# onepiece.net
KiCad netlist of a schematic drawn in EAGLE
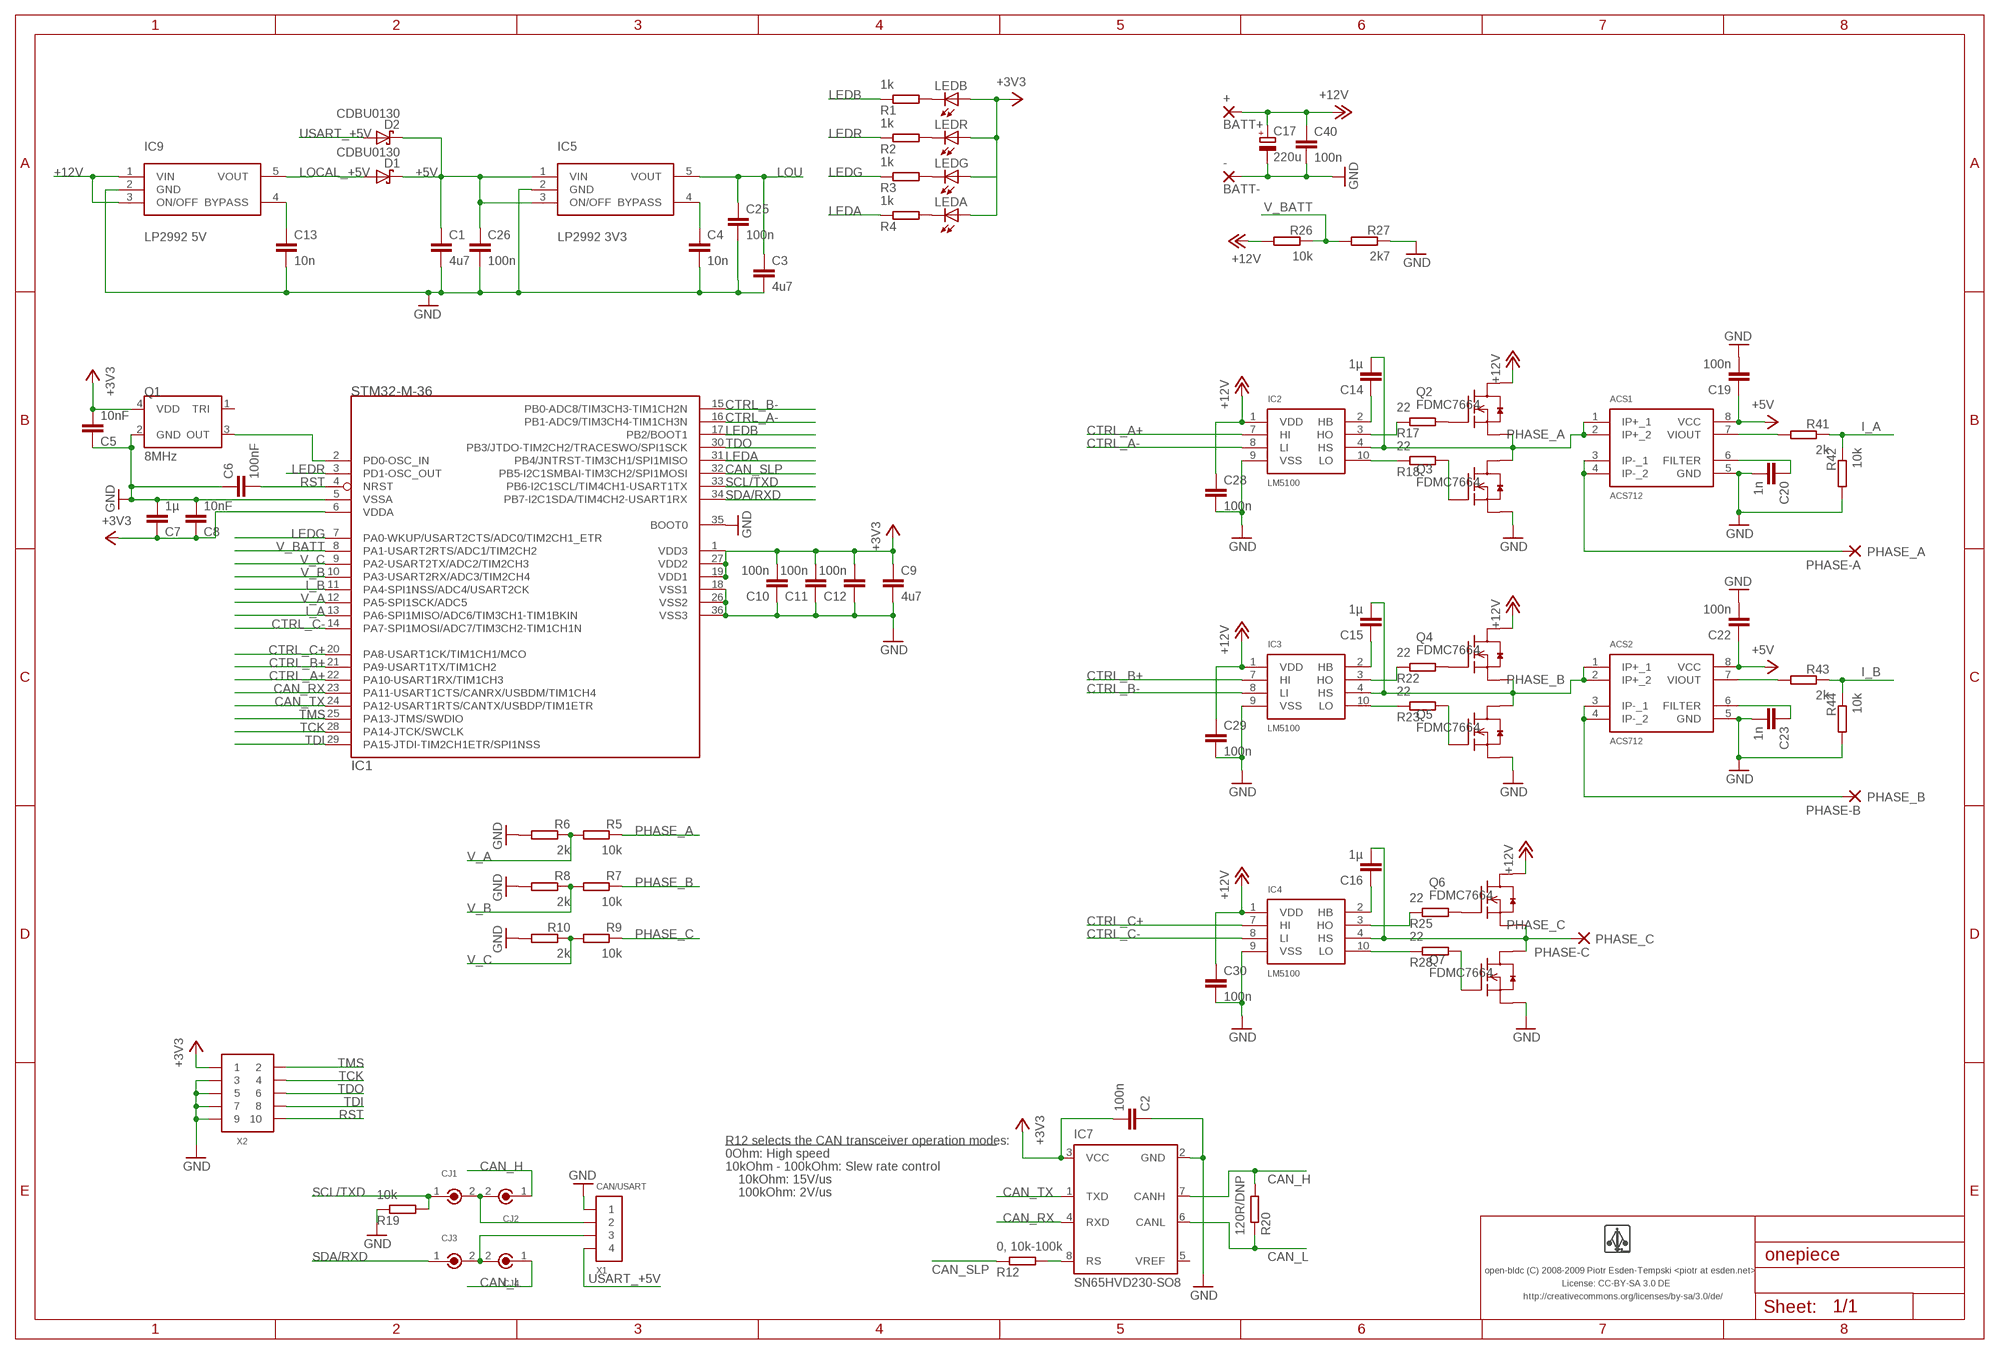
[diagram p0: schematic, sheet 1]

(export (version "E")
  (design (tool "Eeschema 10.0.6"))
  (components
    (comp (ref "+")
      (value "BATT+")
      (footprint "eagle-import:SMD2,54-5,08")
      (libsource (lib "eagle-import") (part "SMD5"))
    )
    (comp (ref "-")
      (value "BATT-")
      (footprint "eagle-import:SMD2,54-5,08")
      (libsource (lib "eagle-import") (part "SMD5"))
    )
    (comp (ref "ACS1")
      (value "ACS712")
      (footprint "eagle-import:SO8")
      (libsource (lib "eagle-import") (part "ACS712"))
    )
    (comp (ref "ACS2")
      (value "ACS712")
      (footprint "eagle-import:SO8")
      (libsource (lib "eagle-import") (part "ACS712"))
    )
    (comp (ref "C1")
      (value "4u7")
      (footprint "eagle-import:0603-CAP")
      (libsource (lib "eagle-import") (part "CAPACITOR-0603"))
    )
    (comp (ref "C2")
      (value "100n")
      (footprint "eagle-import:0603-CAP")
      (libsource (lib "eagle-import") (part "CAPACITOR-0603"))
    )
    (comp (ref "C3")
      (value "4u7")
      (footprint "eagle-import:0603-CAP")
      (libsource (lib "eagle-import") (part "CAPACITOR-0603"))
    )
    (comp (ref "C4")
      (value "10n")
      (footprint "eagle-import:0603-CAP")
      (libsource (lib "eagle-import") (part "CAPACITOR-0603"))
    )
    (comp (ref "C5")
      (value "10nF")
      (footprint "eagle-import:0603-CAP")
      (libsource (lib "eagle-import") (part "CAPACITOR-0603"))
    )
    (comp (ref "C6")
      (value "100nF")
      (footprint "eagle-import:0603-CAP")
      (libsource (lib "eagle-import") (part "CAPACITOR-0603"))
    )
    (comp (ref "C7")
      (value "1µ")
      (footprint "eagle-import:0603-CAP")
      (libsource (lib "eagle-import") (part "CAPACITOR-0603"))
    )
    (comp (ref "C8")
      (value "10nF")
      (footprint "eagle-import:0603-CAP")
      (libsource (lib "eagle-import") (part "CAPACITOR-0603"))
    )
    (comp (ref "C9")
      (value "4u7")
      (footprint "eagle-import:0603-CAP")
      (libsource (lib "eagle-import") (part "CAPACITOR-0603"))
    )
    (comp (ref "C10")
      (value "100n")
      (footprint "eagle-import:0603-CAP")
      (libsource (lib "eagle-import") (part "CAPACITOR-0603"))
    )
    (comp (ref "C11")
      (value "100n")
      (footprint "eagle-import:0603-CAP")
      (libsource (lib "eagle-import") (part "CAPACITOR-0603"))
    )
    (comp (ref "C12")
      (value "100n")
      (footprint "eagle-import:0603-CAP")
      (libsource (lib "eagle-import") (part "CAPACITOR-0603"))
    )
    (comp (ref "C13")
      (value "10n")
      (footprint "eagle-import:0603-CAP")
      (libsource (lib "eagle-import") (part "CAPACITOR-0603"))
    )
    (comp (ref "C14")
      (value "1µ")
      (footprint "eagle-import:0603-CAP")
      (libsource (lib "eagle-import") (part "CAPACITOR-0603"))
    )
    (comp (ref "C15")
      (value "1µ")
      (footprint "eagle-import:0603-CAP")
      (libsource (lib "eagle-import") (part "CAPACITOR-0603"))
    )
    (comp (ref "C16")
      (value "1µ")
      (footprint "eagle-import:0603-CAP")
      (libsource (lib "eagle-import") (part "CAPACITOR-0603"))
    )
    (comp (ref "C17")
      (value "220u")
      (footprint "eagle-import:7343_D")
      (libsource (lib "eagle-import") (part "CAPACITOR-POLD"))
    )
    (comp (ref "C19")
      (value "100n")
      (footprint "eagle-import:0603-CAP")
      (libsource (lib "eagle-import") (part "CAPACITOR-0603"))
    )
    (comp (ref "C20")
      (value "1n")
      (footprint "eagle-import:0603-CAP")
      (libsource (lib "eagle-import") (part "CAPACITOR-0603"))
    )
    (comp (ref "C22")
      (value "100n")
      (footprint "eagle-import:0603-CAP")
      (libsource (lib "eagle-import") (part "CAPACITOR-0603"))
    )
    (comp (ref "C23")
      (value "1n")
      (footprint "eagle-import:0603-CAP")
      (libsource (lib "eagle-import") (part "CAPACITOR-0603"))
    )
    (comp (ref "C25")
      (value "100n")
      (footprint "eagle-import:0603-CAP")
      (libsource (lib "eagle-import") (part "CAPACITOR-0603"))
    )
    (comp (ref "C26")
      (value "100n")
      (footprint "eagle-import:0603-CAP")
      (libsource (lib "eagle-import") (part "CAPACITOR-0603"))
    )
    (comp (ref "C28")
      (value "100n")
      (footprint "eagle-import:0603-CAP")
      (libsource (lib "eagle-import") (part "CAPACITOR-0603"))
    )
    (comp (ref "C29")
      (value "100n")
      (footprint "eagle-import:0603-CAP")
      (libsource (lib "eagle-import") (part "CAPACITOR-0603"))
    )
    (comp (ref "C30")
      (value "100n")
      (footprint "eagle-import:0603-CAP")
      (libsource (lib "eagle-import") (part "CAPACITOR-0603"))
    )
    (comp (ref "C40")
      (value "100n")
      (footprint "eagle-import:0603-CAP")
      (libsource (lib "eagle-import") (part "CAPACITOR-0603"))
    )
    (comp (ref "CJ1")
      (value "CIRC_JMP")
      (footprint "eagle-import:CIRC_JMP")
      (libsource (lib "eagle-import") (part "CIRC_JMP"))
    )
    (comp (ref "CJ2")
      (value "CIRC_JMP")
      (footprint "eagle-import:CIRC_JMP")
      (libsource (lib "eagle-import") (part "CIRC_JMP"))
    )
    (comp (ref "CJ3")
      (value "CIRC_JMP")
      (footprint "eagle-import:CIRC_JMP")
      (libsource (lib "eagle-import") (part "CIRC_JMP"))
    )
    (comp (ref "CJ4")
      (value "CIRC_JMP")
      (footprint "eagle-import:CIRC_JMP")
      (libsource (lib "eagle-import") (part "CIRC_JMP"))
    )
    (comp (ref "D1")
      (value "CDBU0130")
      (footprint "eagle-import:0603-LED")
      (libsource (lib "eagle-import") (part "CDBU0130"))
    )
    (comp (ref "D2")
      (value "CDBU0130")
      (footprint "eagle-import:0603-LED")
      (libsource (lib "eagle-import") (part "CDBU0130"))
    )
    (comp (ref "IC1")
      (value "STM32-M-36")
      (footprint "eagle-import:VFQFPN36-LP")
      (libsource (lib "eagle-import") (part "STM32-M-36"))
    )
    (comp (ref "IC2")
      (value "LM5100")
      (footprint "eagle-import:LLP-10")
      (libsource (lib "eagle-import") (part "LM5100"))
    )
    (comp (ref "IC3")
      (value "LM5100")
      (footprint "eagle-import:LLP-10")
      (libsource (lib "eagle-import") (part "LM5100"))
    )
    (comp (ref "IC4")
      (value "LM5100")
      (footprint "eagle-import:LLP-10")
      (libsource (lib "eagle-import") (part "LM5100"))
    )
    (comp (ref "IC5")
      (value "LP2992 3V3")
      (footprint "eagle-import:SOT23-5")
      (libsource (lib "eagle-import") (part "LP2992"))
    )
    (comp (ref "IC7")
      (value "SN65HVD230-SO8")
      (footprint "eagle-import:SO8")
      (libsource (lib "eagle-import") (part "SN65HVD230"))
    )
    (comp (ref "IC9")
      (value "LP2992 5V")
      (footprint "eagle-import:SOT23-5")
      (libsource (lib "eagle-import") (part "LP2992"))
    )
    (comp (ref "LEDA")
      (value "AMBER")
      (footprint "eagle-import:0603-LED")
      (libsource (lib "eagle-import") (part "LED"))
    )
    (comp (ref "LEDB")
      (value "BLUE")
      (footprint "eagle-import:0603-LED")
      (libsource (lib "eagle-import") (part "LED"))
    )
    (comp (ref "LEDG")
      (value "GREEN")
      (footprint "eagle-import:0603-LED")
      (libsource (lib "eagle-import") (part "LED"))
    )
    (comp (ref "LEDR")
      (value "RED")
      (footprint "eagle-import:0603-LED")
      (libsource (lib "eagle-import") (part "LED"))
    )
    (comp (ref "PHASE-A")
      (value "PHASE_A")
      (footprint "eagle-import:SMD2,54-5,08")
      (libsource (lib "eagle-import") (part "SMD5"))
    )
    (comp (ref "PHASE-B")
      (value "PHASE_B")
      (footprint "eagle-import:SMD2,54-5,08")
      (libsource (lib "eagle-import") (part "SMD5"))
    )
    (comp (ref "PHASE-C")
      (value "PHASE_C")
      (footprint "eagle-import:SMD2,54-5,08")
      (libsource (lib "eagle-import") (part "SMD5"))
    )
    (comp (ref "Q1")
      (value "8MHz")
      (footprint "eagle-import:ASE_OSCILLATOR")
      (libsource (lib "eagle-import") (part "ASE_ASCILLATOR"))
    )
    (comp (ref "Q2")
      (value "FDMC7664")
      (footprint "eagle-import:MLP33")
      (libsource (lib "eagle-import") (part "FDMC7664"))
    )
    (comp (ref "Q3")
      (value "FDMC7664")
      (footprint "eagle-import:MLP33")
      (libsource (lib "eagle-import") (part "FDMC7664"))
    )
    (comp (ref "Q4")
      (value "FDMC7664")
      (footprint "eagle-import:MLP33")
      (libsource (lib "eagle-import") (part "FDMC7664"))
    )
    (comp (ref "Q5")
      (value "FDMC7664")
      (footprint "eagle-import:MLP33")
      (libsource (lib "eagle-import") (part "FDMC7664"))
    )
    (comp (ref "Q6")
      (value "FDMC7664")
      (footprint "eagle-import:MLP33")
      (libsource (lib "eagle-import") (part "FDMC7664"))
    )
    (comp (ref "Q7")
      (value "FDMC7664")
      (footprint "eagle-import:MLP33")
      (libsource (lib "eagle-import") (part "FDMC7664"))
    )
    (comp (ref "R1")
      (value "1k")
      (footprint "eagle-import:0603-RES")
      (libsource (lib "eagle-import") (part "RESISTOR-0603"))
    )
    (comp (ref "R2")
      (value "1k")
      (footprint "eagle-import:0603-RES")
      (libsource (lib "eagle-import") (part "RESISTOR-0603"))
    )
    (comp (ref "R3")
      (value "1k")
      (footprint "eagle-import:0603-RES")
      (libsource (lib "eagle-import") (part "RESISTOR-0603"))
    )
    (comp (ref "R4")
      (value "1k")
      (footprint "eagle-import:0603-RES")
      (libsource (lib "eagle-import") (part "RESISTOR-0603"))
    )
    (comp (ref "R5")
      (value "10k")
      (footprint "eagle-import:0603-RES")
      (libsource (lib "eagle-import") (part "RESISTOR-0603"))
    )
    (comp (ref "R6")
      (value "2k")
      (footprint "eagle-import:0603-RES")
      (libsource (lib "eagle-import") (part "RESISTOR-0603"))
    )
    (comp (ref "R7")
      (value "10k")
      (footprint "eagle-import:0603-RES")
      (libsource (lib "eagle-import") (part "RESISTOR-0603"))
    )
    (comp (ref "R8")
      (value "2k")
      (footprint "eagle-import:0603-RES")
      (libsource (lib "eagle-import") (part "RESISTOR-0603"))
    )
    (comp (ref "R9")
      (value "10k")
      (footprint "eagle-import:0603-RES")
      (libsource (lib "eagle-import") (part "RESISTOR-0603"))
    )
    (comp (ref "R10")
      (value "2k")
      (footprint "eagle-import:0603-RES")
      (libsource (lib "eagle-import") (part "RESISTOR-0603"))
    )
    (comp (ref "R12")
      (value "0, 10k-100k")
      (footprint "eagle-import:0603-RES")
      (libsource (lib "eagle-import") (part "RESISTOR-0603"))
    )
    (comp (ref "R17")
      (value "22")
      (footprint "eagle-import:0603-RES")
      (libsource (lib "eagle-import") (part "RESISTOR-0603"))
    )
    (comp (ref "R18")
      (value "22")
      (footprint "eagle-import:0603-RES")
      (libsource (lib "eagle-import") (part "RESISTOR-0603"))
    )
    (comp (ref "R19")
      (value "10k")
      (footprint "eagle-import:0603-RES")
      (libsource (lib "eagle-import") (part "RESISTOR-0603"))
    )
    (comp (ref "R20")
      (value "120R/DNP")
      (footprint "eagle-import:0603-RES")
      (libsource (lib "eagle-import") (part "RESISTOR-0603"))
    )
    (comp (ref "R22")
      (value "22")
      (footprint "eagle-import:0603-RES")
      (libsource (lib "eagle-import") (part "RESISTOR-0603"))
    )
    (comp (ref "R23")
      (value "22")
      (footprint "eagle-import:0603-RES")
      (libsource (lib "eagle-import") (part "RESISTOR-0603"))
    )
    (comp (ref "R25")
      (value "22")
      (footprint "eagle-import:0603-RES")
      (libsource (lib "eagle-import") (part "RESISTOR-0603"))
    )
    (comp (ref "R26")
      (value "10k")
      (footprint "eagle-import:0603-RES")
      (libsource (lib "eagle-import") (part "RESISTOR-0603"))
    )
    (comp (ref "R27")
      (value "2k7")
      (footprint "eagle-import:0603-RES")
      (libsource (lib "eagle-import") (part "RESISTOR-0603"))
    )
    (comp (ref "R28")
      (value "22")
      (footprint "eagle-import:0603-RES")
      (libsource (lib "eagle-import") (part "RESISTOR-0603"))
    )
    (comp (ref "R41")
      (value "2k")
      (footprint "eagle-import:0603-RES")
      (libsource (lib "eagle-import") (part "RESISTOR-0603"))
    )
    (comp (ref "R42")
      (value "10k")
      (footprint "eagle-import:0603-RES")
      (libsource (lib "eagle-import") (part "RESISTOR-0603"))
    )
    (comp (ref "R43")
      (value "2k")
      (footprint "eagle-import:0603-RES")
      (libsource (lib "eagle-import") (part "RESISTOR-0603"))
    )
    (comp (ref "R44")
      (value "10k")
      (footprint "eagle-import:0603-RES")
      (libsource (lib "eagle-import") (part "RESISTOR-0603"))
    )
    (comp (ref "U$1")
      (value "LOGO")
      (footprint "eagle-import:LOGO_SMALL")
      (libsource (lib "eagle-import") (part "LOGO-SMALL"))
    )
    (comp (ref "X1")
      (value "CAN/USART")
      (footprint "eagle-import:PB-53261-04")
      (libsource (lib "eagle-import") (part "CONN_4-1-53261"))
    )
    (comp (ref "X2")
      (value "PIN_HDR_EDG_1.27MM_5-2")
      (footprint "eagle-import:PIN_HDR_1.27MM_SMD_DH_10")
      (libsource (lib "eagle-import") (part "PIN_HDR_EDG_1.27MM_5-2-DH"))
    )
  )
  (nets
    (net (code "1") (name "+3V3") (class "Default")
      (node (ref "C10") (pin "P$2") (pinfunction "2_P$2") (pintype "passive"))
      (node (ref "C11") (pin "P$2") (pinfunction "2_P$2") (pintype "passive"))
      (node (ref "C12") (pin "P$2") (pinfunction "2_P$2") (pintype "passive"))
      (node (ref "C2") (pin "P$2") (pinfunction "2_P$2") (pintype "passive"))
      (node (ref "C25") (pin "P$1") (pinfunction "1_P$1") (pintype "passive"))
      (node (ref "C3") (pin "P$1") (pinfunction "1_P$1") (pintype "passive"))
      (node (ref "C5") (pin "P$2") (pinfunction "2_P$2") (pintype "passive"))
      (node (ref "C7") (pin "P$1") (pinfunction "1_P$1") (pintype "passive"))
      (node (ref "C8") (pin "P$1") (pinfunction "1_P$1") (pintype "passive"))
      (node (ref "C9") (pin "P$1") (pinfunction "1_P$1") (pintype "passive"))
      (node (ref "IC1") (pin "1") (pinfunction "VDD3_1") (pintype "power_in"))
      (node (ref "IC1") (pin "19") (pinfunction "VDD1_19") (pintype "power_in"))
      (node (ref "IC1") (pin "27") (pinfunction "VDD2_27") (pintype "power_in"))
      (node (ref "IC1") (pin "6") (pinfunction "VDDA_6") (pintype "power_in"))
      (node (ref "IC5") (pin "5") (pinfunction "VOUT_5") (pintype "bidirectional"))
      (node (ref "IC7") (pin "3") (pinfunction "VCC_3") (pintype "power_in"))
      (node (ref "LEDA") (pin "A") (pinfunction "A_A") (pintype "passive"))
      (node (ref "LEDB") (pin "A") (pinfunction "A_A") (pintype "passive"))
      (node (ref "LEDG") (pin "A") (pinfunction "A_A") (pintype "passive"))
      (node (ref "LEDR") (pin "A") (pinfunction "A_A") (pintype "passive"))
      (node (ref "Q1") (pin "4") (pinfunction "VDD_4") (pintype "power_in"))
      (node (ref "X2") (pin "1") (pinfunction "1_1") (pintype "bidirectional"))
    )
    (net (code "2") (name "+5V") (class "Default")
      (node (ref "ACS1") (pin "8") (pinfunction "VCC_8") (pintype "bidirectional"))
      (node (ref "ACS2") (pin "8") (pinfunction "VCC_8") (pintype "bidirectional"))
      (node (ref "C1") (pin "P$1") (pinfunction "1_P$1") (pintype "passive"))
      (node (ref "C19") (pin "P$1") (pinfunction "1_P$1") (pintype "passive"))
      (node (ref "C22") (pin "P$1") (pinfunction "1_P$1") (pintype "passive"))
      (node (ref "C26") (pin "P$1") (pinfunction "1_P$1") (pintype "passive"))
      (node (ref "D1") (pin "C") (pinfunction "C_C") (pintype "passive"))
      (node (ref "D2") (pin "C") (pinfunction "C_C") (pintype "passive"))
      (node (ref "IC5") (pin "1") (pinfunction "VIN_1") (pintype "bidirectional"))
      (node (ref "IC5") (pin "3") (pinfunction "ON/OFF_3") (pintype "bidirectional"))
    )
    (net (code "3") (name "+12V") (class "Default")
      (node (ref "+") (pin "1") (pinfunction "P_1") (pintype "passive"))
      (node (ref "C17") (pin "+") (pinfunction "+_+") (pintype "passive"))
      (node (ref "C28") (pin "P$1") (pinfunction "1_P$1") (pintype "passive"))
      (node (ref "C29") (pin "P$1") (pinfunction "1_P$1") (pintype "passive"))
      (node (ref "C30") (pin "P$1") (pinfunction "1_P$1") (pintype "passive"))
      (node (ref "C40") (pin "P$1") (pinfunction "1_P$1") (pintype "passive"))
      (node (ref "IC2") (pin "1") (pinfunction "VDD_1") (pintype "bidirectional"))
      (node (ref "IC3") (pin "1") (pinfunction "VDD_1") (pintype "bidirectional"))
      (node (ref "IC4") (pin "1") (pinfunction "VDD_1") (pintype "bidirectional"))
      (node (ref "IC9") (pin "1") (pinfunction "VIN_1") (pintype "bidirectional"))
      (node (ref "IC9") (pin "3") (pinfunction "ON/OFF_3") (pintype "bidirectional"))
      (node (ref "Q2") (pin "5678D") (pinfunction "D_5678D") (pintype "passive"))
      (node (ref "Q4") (pin "5678D") (pinfunction "D_5678D") (pintype "passive"))
      (node (ref "Q6") (pin "5678D") (pinfunction "D_5678D") (pintype "passive"))
      (node (ref "R26") (pin "P$2") (pinfunction "2_P$2") (pintype "passive"))
    )
    (net (code "4") (name "/CAN_H") (class "Default")
      (node (ref "CJ2") (pin "1") (pinfunction "P$1_1") (pintype "bidirectional"))
      (node (ref "IC7") (pin "7") (pinfunction "CANH_7") (pintype "bidirectional"))
      (node (ref "R20") (pin "P$2") (pinfunction "2_P$2") (pintype "passive"))
    )
    (net (code "5") (name "/CAN_L") (class "Default")
      (node (ref "CJ4") (pin "1") (pinfunction "P$1_1") (pintype "bidirectional"))
      (node (ref "IC7") (pin "6") (pinfunction "CANL_6") (pintype "bidirectional"))
      (node (ref "R20") (pin "P$1") (pinfunction "1_P$1") (pintype "passive"))
    )
    (net (code "6") (name "/CAN_RX") (class "Default")
      (node (ref "IC1") (pin "23") (pinfunction "PA11-USART1CTS/CANRX/USBDM/TIM1CH4_23") (pintype "bidirectional"))
      (node (ref "IC7") (pin "4") (pinfunction "RXD_4") (pintype "output"))
    )
    (net (code "7") (name "/CAN_SLP") (class "Default")
      (node (ref "IC1") (pin "32") (pinfunction "PB5-I2C1SMBAI-TIM3CH2/SPI1MOSI_32") (pintype "bidirectional"))
      (node (ref "R12") (pin "P$1") (pinfunction "1_P$1") (pintype "passive"))
    )
    (net (code "8") (name "/CAN_TX") (class "Default")
      (node (ref "IC1") (pin "24") (pinfunction "PA12-USART1RTS/CANTX/USBDP/TIM1ETR_24") (pintype "bidirectional"))
      (node (ref "IC7") (pin "1") (pinfunction "TXD_1") (pintype "input"))
    )
    (net (code "9") (name "/CTRL_A+") (class "Default")
      (node (ref "IC1") (pin "22") (pinfunction "PA10-USART1RX/TIM1CH3_22") (pintype "bidirectional"))
      (node (ref "IC2") (pin "7") (pinfunction "HI_7") (pintype "bidirectional"))
    )
    (net (code "10") (name "/CTRL_A-") (class "Default")
      (node (ref "IC1") (pin "16") (pinfunction "PB1-ADC9/TIM3CH4-TIM1CH3N_16") (pintype "bidirectional"))
      (node (ref "IC2") (pin "8") (pinfunction "LI_8") (pintype "bidirectional"))
    )
    (net (code "11") (name "/CTRL_B+") (class "Default")
      (node (ref "IC1") (pin "21") (pinfunction "PA9-USART1TX/TIM1CH2_21") (pintype "bidirectional"))
      (node (ref "IC3") (pin "7") (pinfunction "HI_7") (pintype "bidirectional"))
    )
    (net (code "12") (name "/CTRL_B-") (class "Default")
      (node (ref "IC1") (pin "15") (pinfunction "PB0-ADC8/TIM3CH3-TIM1CH2N_15") (pintype "bidirectional"))
      (node (ref "IC3") (pin "8") (pinfunction "LI_8") (pintype "bidirectional"))
    )
    (net (code "13") (name "/CTRL_C+") (class "Default")
      (node (ref "IC1") (pin "20") (pinfunction "PA8-USART1CK/TIM1CH1/MCO_20") (pintype "bidirectional"))
      (node (ref "IC4") (pin "7") (pinfunction "HI_7") (pintype "bidirectional"))
    )
    (net (code "14") (name "/CTRL_C-") (class "Default")
      (node (ref "IC1") (pin "14") (pinfunction "PA7-SPI1MOSI/ADC7/TIM3CH2-TIM1CH1N_14") (pintype "bidirectional"))
      (node (ref "IC4") (pin "8") (pinfunction "LI_8") (pintype "bidirectional"))
    )
    (net (code "15") (name "/I_A") (class "Default")
      (node (ref "IC1") (pin "13") (pinfunction "PA6-SPI1MISO/ADC6/TIM3CH1-TIM1BKIN_13") (pintype "bidirectional"))
      (node (ref "R41") (pin "P$1") (pinfunction "1_P$1") (pintype "passive"))
      (node (ref "R42") (pin "P$1") (pinfunction "1_P$1") (pintype "passive"))
    )
    (net (code "16") (name "/I_B") (class "Default")
      (node (ref "IC1") (pin "11") (pinfunction "PA4-SPI1NSS/ADC4/USART2CK_11") (pintype "bidirectional"))
      (node (ref "R43") (pin "P$1") (pinfunction "1_P$1") (pintype "passive"))
      (node (ref "R44") (pin "P$1") (pinfunction "1_P$1") (pintype "passive"))
    )
    (net (code "17") (name "/LEDA") (class "Default")
      (node (ref "IC1") (pin "31") (pinfunction "PB4/JNTRST-TIM3CH1/SPI1MISO_31") (pintype "bidirectional"))
      (node (ref "R4") (pin "P$1") (pinfunction "1_P$1") (pintype "passive"))
    )
    (net (code "18") (name "/LEDB") (class "Default")
      (node (ref "IC1") (pin "17") (pinfunction "PB2/BOOT1_17") (pintype "bidirectional"))
      (node (ref "R1") (pin "P$1") (pinfunction "1_P$1") (pintype "passive"))
    )
    (net (code "19") (name "/LEDG") (class "Default")
      (node (ref "IC1") (pin "7") (pinfunction "PA0-WKUP/USART2CTS/ADC0/TIM2CH1_ETR_7") (pintype "bidirectional"))
      (node (ref "R3") (pin "P$1") (pinfunction "1_P$1") (pintype "passive"))
    )
    (net (code "20") (name "/LEDR") (class "Default")
      (node (ref "IC1") (pin "3") (pinfunction "PD1-OSC_OUT_3") (pintype "output"))
      (node (ref "R2") (pin "P$1") (pinfunction "1_P$1") (pintype "passive"))
    )
    (net (code "21") (name "/LOCAL_+5V") (class "Default")
      (node (ref "D1") (pin "A") (pinfunction "A_A") (pintype "passive"))
      (node (ref "IC9") (pin "5") (pinfunction "VOUT_5") (pintype "bidirectional"))
    )
    (net (code "22") (name "/PHASE_A") (class "Default")
      (node (ref "ACS1") (pin "1") (pinfunction "IP+_1_1") (pintype "bidirectional"))
      (node (ref "ACS1") (pin "2") (pinfunction "IP+_2_2") (pintype "bidirectional"))
      (node (ref "C14") (pin "P$2") (pinfunction "2_P$2") (pintype "passive"))
      (node (ref "IC2") (pin "4") (pinfunction "HS_4") (pintype "bidirectional"))
      (node (ref "Q2") (pin "123S") (pinfunction "S_123S") (pintype "passive"))
      (node (ref "Q3") (pin "5678D") (pinfunction "D_5678D") (pintype "passive"))
      (node (ref "R5") (pin "P$1") (pinfunction "1_P$1") (pintype "passive"))
    )
    (net (code "23") (name "/PHASE_B") (class "Default")
      (node (ref "ACS2") (pin "1") (pinfunction "IP+_1_1") (pintype "bidirectional"))
      (node (ref "ACS2") (pin "2") (pinfunction "IP+_2_2") (pintype "bidirectional"))
      (node (ref "C15") (pin "P$2") (pinfunction "2_P$2") (pintype "passive"))
      (node (ref "IC3") (pin "4") (pinfunction "HS_4") (pintype "bidirectional"))
      (node (ref "Q4") (pin "123S") (pinfunction "S_123S") (pintype "passive"))
      (node (ref "Q5") (pin "5678D") (pinfunction "D_5678D") (pintype "passive"))
      (node (ref "R7") (pin "P$1") (pinfunction "1_P$1") (pintype "passive"))
    )
    (net (code "24") (name "/PHASE_C") (class "Default")
      (node (ref "C16") (pin "P$2") (pinfunction "2_P$2") (pintype "passive"))
      (node (ref "IC4") (pin "4") (pinfunction "HS_4") (pintype "bidirectional"))
      (node (ref "PHASE-C") (pin "1") (pinfunction "P_1") (pintype "passive"))
      (node (ref "Q6") (pin "123S") (pinfunction "S_123S") (pintype "passive"))
      (node (ref "Q7") (pin "5678D") (pinfunction "D_5678D") (pintype "passive"))
      (node (ref "R9") (pin "P$1") (pinfunction "1_P$1") (pintype "passive"))
    )
    (net (code "25") (name "/RST") (class "Default")
      (node (ref "C6") (pin "P$2") (pinfunction "2_P$2") (pintype "passive"))
      (node (ref "IC1") (pin "4") (pinfunction "NRST_4") (pintype "bidirectional"))
      (node (ref "X2") (pin "10") (pinfunction "10_10") (pintype "bidirectional"))
    )
    (net (code "26") (name "/SCL{slash}TXD") (class "Default")
      (node (ref "CJ1") (pin "1") (pinfunction "P$1_1") (pintype "bidirectional"))
      (node (ref "IC1") (pin "33") (pinfunction "PB6-I2C1SCL/TIM4CH1-USART1TX_33") (pintype "bidirectional"))
      (node (ref "R19") (pin "P$2") (pinfunction "2_P$2") (pintype "passive"))
    )
    (net (code "27") (name "/SDA{slash}RXD") (class "Default")
      (node (ref "CJ3") (pin "1") (pinfunction "P$1_1") (pintype "bidirectional"))
      (node (ref "IC1") (pin "34") (pinfunction "PB7-I2C1SDA/TIM4CH2-USART1RX_34") (pintype "bidirectional"))
    )
    (net (code "28") (name "/TCK") (class "Default")
      (node (ref "IC1") (pin "28") (pinfunction "PA14-JTCK/SWCLK_28") (pintype "bidirectional"))
      (node (ref "X2") (pin "4") (pinfunction "4_4") (pintype "bidirectional"))
    )
    (net (code "29") (name "/TDI") (class "Default")
      (node (ref "IC1") (pin "29") (pinfunction "PA15-JTDI-TIM2CH1ETR/SPI1NSS_29") (pintype "bidirectional"))
      (node (ref "X2") (pin "8") (pinfunction "8_8") (pintype "bidirectional"))
    )
    (net (code "30") (name "/TDO") (class "Default")
      (node (ref "IC1") (pin "30") (pinfunction "PB3/JTDO-TIM2CH2/TRACESWO/SPI1SCK_30") (pintype "bidirectional"))
      (node (ref "X2") (pin "6") (pinfunction "6_6") (pintype "bidirectional"))
    )
    (net (code "31") (name "/TMS") (class "Default")
      (node (ref "IC1") (pin "25") (pinfunction "PA13-JTMS/SWDIO_25") (pintype "bidirectional"))
      (node (ref "X2") (pin "2") (pinfunction "2_2") (pintype "bidirectional"))
    )
    (net (code "32") (name "/USART_+5V") (class "Default")
      (node (ref "D2") (pin "A") (pinfunction "A_A") (pintype "passive"))
      (node (ref "X1") (pin "4") (pinfunction "4_4") (pintype "bidirectional"))
    )
    (net (code "33") (name "/V_A") (class "Default")
      (node (ref "IC1") (pin "12") (pinfunction "PA5-SPI1SCK/ADC5_12") (pintype "bidirectional"))
      (node (ref "R5") (pin "P$2") (pinfunction "2_P$2") (pintype "passive"))
      (node (ref "R6") (pin "P$1") (pinfunction "1_P$1") (pintype "passive"))
    )
    (net (code "34") (name "/V_B") (class "Default")
      (node (ref "IC1") (pin "10") (pinfunction "PA3-USART2RX/ADC3/TIM2CH4_10") (pintype "bidirectional"))
      (node (ref "R7") (pin "P$2") (pinfunction "2_P$2") (pintype "passive"))
      (node (ref "R8") (pin "P$1") (pinfunction "1_P$1") (pintype "passive"))
    )
    (net (code "35") (name "/V_BATT") (class "Default")
      (node (ref "IC1") (pin "8") (pinfunction "PA1-USART2RTS/ADC1/TIM2CH2_8") (pintype "bidirectional"))
      (node (ref "R26") (pin "P$1") (pinfunction "1_P$1") (pintype "passive"))
      (node (ref "R27") (pin "P$2") (pinfunction "2_P$2") (pintype "passive"))
    )
    (net (code "36") (name "/V_C") (class "Default")
      (node (ref "IC1") (pin "9") (pinfunction "PA2-USART2TX/ADC2/TIM2CH3_9") (pintype "bidirectional"))
      (node (ref "R10") (pin "P$1") (pinfunction "1_P$1") (pintype "passive"))
      (node (ref "R9") (pin "P$2") (pinfunction "2_P$2") (pintype "passive"))
    )
    (net (code "37") (name "GND") (class "Default")
      (node (ref "-") (pin "1") (pinfunction "P_1") (pintype "passive"))
      (node (ref "ACS1") (pin "5") (pinfunction "GND_5") (pintype "bidirectional"))
      (node (ref "ACS2") (pin "5") (pinfunction "GND_5") (pintype "bidirectional"))
      (node (ref "C1") (pin "P$2") (pinfunction "2_P$2") (pintype "passive"))
      (node (ref "C10") (pin "P$1") (pinfunction "1_P$1") (pintype "passive"))
      (node (ref "C11") (pin "P$1") (pinfunction "1_P$1") (pintype "passive"))
      (node (ref "C12") (pin "P$1") (pinfunction "1_P$1") (pintype "passive"))
      (node (ref "C13") (pin "P$2") (pinfunction "2_P$2") (pintype "passive"))
      (node (ref "C17") (pin "-") (pinfunction "-_-") (pintype "passive"))
      (node (ref "C19") (pin "P$2") (pinfunction "2_P$2") (pintype "passive"))
      (node (ref "C2") (pin "P$1") (pinfunction "1_P$1") (pintype "passive"))
      (node (ref "C20") (pin "P$2") (pinfunction "2_P$2") (pintype "passive"))
      (node (ref "C22") (pin "P$2") (pinfunction "2_P$2") (pintype "passive"))
      (node (ref "C23") (pin "P$2") (pinfunction "2_P$2") (pintype "passive"))
      (node (ref "C25") (pin "P$2") (pinfunction "2_P$2") (pintype "passive"))
      (node (ref "C26") (pin "P$2") (pinfunction "2_P$2") (pintype "passive"))
      (node (ref "C28") (pin "P$2") (pinfunction "2_P$2") (pintype "passive"))
      (node (ref "C29") (pin "P$2") (pinfunction "2_P$2") (pintype "passive"))
      (node (ref "C3") (pin "P$2") (pinfunction "2_P$2") (pintype "passive"))
      (node (ref "C30") (pin "P$2") (pinfunction "2_P$2") (pintype "passive"))
      (node (ref "C4") (pin "P$2") (pinfunction "2_P$2") (pintype "passive"))
      (node (ref "C40") (pin "P$2") (pinfunction "2_P$2") (pintype "passive"))
      (node (ref "C5") (pin "P$1") (pinfunction "1_P$1") (pintype "passive"))
      (node (ref "C6") (pin "P$1") (pinfunction "1_P$1") (pintype "passive"))
      (node (ref "C7") (pin "P$2") (pinfunction "2_P$2") (pintype "passive"))
      (node (ref "C8") (pin "P$2") (pinfunction "2_P$2") (pintype "passive"))
      (node (ref "C9") (pin "P$2") (pinfunction "2_P$2") (pintype "passive"))
      (node (ref "IC1") (pin "18") (pinfunction "VSS1_18") (pintype "power_in"))
      (node (ref "IC1") (pin "26") (pinfunction "VSS2_26") (pintype "power_in"))
      (node (ref "IC1") (pin "35") (pinfunction "BOOT0_35") (pintype "input"))
      (node (ref "IC1") (pin "36") (pinfunction "VSS3_36") (pintype "power_in"))
      (node (ref "IC1") (pin "5") (pinfunction "VSSA_5") (pintype "power_in"))
      (node (ref "IC2") (pin "9") (pinfunction "VSS_9") (pintype "bidirectional"))
      (node (ref "IC3") (pin "9") (pinfunction "VSS_9") (pintype "bidirectional"))
      (node (ref "IC4") (pin "9") (pinfunction "VSS_9") (pintype "bidirectional"))
      (node (ref "IC5") (pin "2") (pinfunction "GND_2") (pintype "bidirectional"))
      (node (ref "IC7") (pin "2") (pinfunction "GND_2") (pintype "power_in"))
      (node (ref "IC9") (pin "2") (pinfunction "GND_2") (pintype "bidirectional"))
      (node (ref "Q1") (pin "2") (pinfunction "GND_2") (pintype "power_in"))
      (node (ref "Q3") (pin "123S") (pinfunction "S_123S") (pintype "passive"))
      (node (ref "Q5") (pin "123S") (pinfunction "S_123S") (pintype "passive"))
      (node (ref "Q7") (pin "123S") (pinfunction "S_123S") (pintype "passive"))
      (node (ref "R10") (pin "P$2") (pinfunction "2_P$2") (pintype "passive"))
      (node (ref "R19") (pin "P$1") (pinfunction "1_P$1") (pintype "passive"))
      (node (ref "R27") (pin "P$1") (pinfunction "1_P$1") (pintype "passive"))
      (node (ref "R42") (pin "P$2") (pinfunction "2_P$2") (pintype "passive"))
      (node (ref "R44") (pin "P$2") (pinfunction "2_P$2") (pintype "passive"))
      (node (ref "R6") (pin "P$2") (pinfunction "2_P$2") (pintype "passive"))
      (node (ref "R8") (pin "P$2") (pinfunction "2_P$2") (pintype "passive"))
      (node (ref "X1") (pin "1") (pinfunction "1_1") (pintype "bidirectional"))
      (node (ref "X2") (pin "3") (pinfunction "3_3") (pintype "bidirectional"))
      (node (ref "X2") (pin "5") (pinfunction "5_5") (pintype "bidirectional"))
      (node (ref "X2") (pin "7") (pinfunction "7_7") (pintype "bidirectional"))
      (node (ref "X2") (pin "9") (pinfunction "9_9") (pintype "bidirectional"))
    )
    (net (code "38") (name "Net-(ACS1-FILTER)") (class "Default")
      (node (ref "ACS1") (pin "6") (pinfunction "FILTER_6") (pintype "bidirectional"))
      (node (ref "C20") (pin "P$1") (pinfunction "1_P$1") (pintype "passive"))
    )
    (net (code "39") (name "Net-(ACS1-IP-_1)") (class "Default")
      (node (ref "ACS1") (pin "3") (pinfunction "IP-_1_3") (pintype "bidirectional"))
      (node (ref "ACS1") (pin "4") (pinfunction "IP-_2_4") (pintype "bidirectional"))
      (node (ref "PHASE-A") (pin "1") (pinfunction "P_1") (pintype "passive"))
    )
    (net (code "40") (name "Net-(ACS1-VIOUT)") (class "Default")
      (node (ref "ACS1") (pin "7") (pinfunction "VIOUT_7") (pintype "bidirectional"))
      (node (ref "R41") (pin "P$2") (pinfunction "2_P$2") (pintype "passive"))
    )
    (net (code "41") (name "Net-(ACS2-FILTER)") (class "Default")
      (node (ref "ACS2") (pin "6") (pinfunction "FILTER_6") (pintype "bidirectional"))
      (node (ref "C23") (pin "P$1") (pinfunction "1_P$1") (pintype "passive"))
    )
    (net (code "42") (name "Net-(ACS2-IP-_1)") (class "Default")
      (node (ref "ACS2") (pin "3") (pinfunction "IP-_1_3") (pintype "bidirectional"))
      (node (ref "ACS2") (pin "4") (pinfunction "IP-_2_4") (pintype "bidirectional"))
      (node (ref "PHASE-B") (pin "1") (pinfunction "P_1") (pintype "passive"))
    )
    (net (code "43") (name "Net-(ACS2-VIOUT)") (class "Default")
      (node (ref "ACS2") (pin "7") (pinfunction "VIOUT_7") (pintype "bidirectional"))
      (node (ref "R43") (pin "P$2") (pinfunction "2_P$2") (pintype "passive"))
    )
    (net (code "44") (name "Net-(C4-1)") (class "Default")
      (node (ref "C4") (pin "P$1") (pinfunction "1_P$1") (pintype "passive"))
      (node (ref "IC5") (pin "4") (pinfunction "BYPASS_4") (pintype "bidirectional"))
    )
    (net (code "45") (name "Net-(C13-1)") (class "Default")
      (node (ref "C13") (pin "P$1") (pinfunction "1_P$1") (pintype "passive"))
      (node (ref "IC9") (pin "4") (pinfunction "BYPASS_4") (pintype "bidirectional"))
    )
    (net (code "46") (name "Net-(C14-1)") (class "Default")
      (node (ref "C14") (pin "P$1") (pinfunction "1_P$1") (pintype "passive"))
      (node (ref "IC2") (pin "2") (pinfunction "HB_2") (pintype "bidirectional"))
    )
    (net (code "47") (name "Net-(C15-1)") (class "Default")
      (node (ref "C15") (pin "P$1") (pinfunction "1_P$1") (pintype "passive"))
      (node (ref "IC3") (pin "2") (pinfunction "HB_2") (pintype "bidirectional"))
    )
    (net (code "48") (name "Net-(C16-1)") (class "Default")
      (node (ref "C16") (pin "P$1") (pinfunction "1_P$1") (pintype "passive"))
      (node (ref "IC4") (pin "2") (pinfunction "HB_2") (pintype "bidirectional"))
    )
    (net (code "49") (name "Net-(CJ1-P$2)") (class "Default")
      (node (ref "CJ1") (pin "2") (pinfunction "P$2_2") (pintype "bidirectional"))
      (node (ref "CJ2") (pin "2") (pinfunction "P$2_2") (pintype "bidirectional"))
      (node (ref "X1") (pin "2") (pinfunction "2_2") (pintype "bidirectional"))
    )
    (net (code "50") (name "Net-(CJ3-P$2)") (class "Default")
      (node (ref "CJ3") (pin "2") (pinfunction "P$2_2") (pintype "bidirectional"))
      (node (ref "CJ4") (pin "2") (pinfunction "P$2_2") (pintype "bidirectional"))
      (node (ref "X1") (pin "3") (pinfunction "3_3") (pintype "bidirectional"))
    )
    (net (code "51") (name "Net-(IC1-PD0-OSC_IN)") (class "Default")
      (node (ref "IC1") (pin "2") (pinfunction "PD0-OSC_IN_2") (pintype "input"))
      (node (ref "Q1") (pin "3") (pinfunction "OUT_3") (pintype "output"))
    )
    (net (code "52") (name "Net-(IC2-HO)") (class "Default")
      (node (ref "IC2") (pin "3") (pinfunction "HO_3") (pintype "bidirectional"))
      (node (ref "R17") (pin "P$1") (pinfunction "1_P$1") (pintype "passive"))
    )
    (net (code "53") (name "Net-(IC2-LO)") (class "Default")
      (node (ref "IC2") (pin "10") (pinfunction "LO_10") (pintype "bidirectional"))
      (node (ref "R18") (pin "P$1") (pinfunction "1_P$1") (pintype "passive"))
    )
    (net (code "54") (name "Net-(IC3-HO)") (class "Default")
      (node (ref "IC3") (pin "3") (pinfunction "HO_3") (pintype "bidirectional"))
      (node (ref "R22") (pin "P$1") (pinfunction "1_P$1") (pintype "passive"))
    )
    (net (code "55") (name "Net-(IC3-LO)") (class "Default")
      (node (ref "IC3") (pin "10") (pinfunction "LO_10") (pintype "bidirectional"))
      (node (ref "R23") (pin "P$1") (pinfunction "1_P$1") (pintype "passive"))
    )
    (net (code "56") (name "Net-(IC4-HO)") (class "Default")
      (node (ref "IC4") (pin "3") (pinfunction "HO_3") (pintype "bidirectional"))
      (node (ref "R25") (pin "P$1") (pinfunction "1_P$1") (pintype "passive"))
    )
    (net (code "57") (name "Net-(IC4-LO)") (class "Default")
      (node (ref "IC4") (pin "10") (pinfunction "LO_10") (pintype "bidirectional"))
      (node (ref "R28") (pin "P$1") (pinfunction "1_P$1") (pintype "passive"))
    )
    (net (code "58") (name "Net-(IC7-RS)") (class "Default")
      (node (ref "IC7") (pin "8") (pinfunction "RS_8") (pintype "input"))
      (node (ref "R12") (pin "P$2") (pinfunction "2_P$2") (pintype "passive"))
    )
    (net (code "59") (name "Net-(Q2-G)") (class "Default")
      (node (ref "Q2") (pin "4G") (pinfunction "G_4G") (pintype "passive"))
      (node (ref "R17") (pin "P$2") (pinfunction "2_P$2") (pintype "passive"))
    )
    (net (code "60") (name "Net-(Q3-G)") (class "Default")
      (node (ref "Q3") (pin "4G") (pinfunction "G_4G") (pintype "passive"))
      (node (ref "R18") (pin "P$2") (pinfunction "2_P$2") (pintype "passive"))
    )
    (net (code "61") (name "Net-(Q4-G)") (class "Default")
      (node (ref "Q4") (pin "4G") (pinfunction "G_4G") (pintype "passive"))
      (node (ref "R22") (pin "P$2") (pinfunction "2_P$2") (pintype "passive"))
    )
    (net (code "62") (name "Net-(Q5-G)") (class "Default")
      (node (ref "Q5") (pin "4G") (pinfunction "G_4G") (pintype "passive"))
      (node (ref "R23") (pin "P$2") (pinfunction "2_P$2") (pintype "passive"))
    )
    (net (code "63") (name "Net-(Q6-G)") (class "Default")
      (node (ref "Q6") (pin "4G") (pinfunction "G_4G") (pintype "passive"))
      (node (ref "R25") (pin "P$2") (pinfunction "2_P$2") (pintype "passive"))
    )
    (net (code "64") (name "Net-(Q7-G)") (class "Default")
      (node (ref "Q7") (pin "4G") (pinfunction "G_4G") (pintype "passive"))
      (node (ref "R28") (pin "P$2") (pinfunction "2_P$2") (pintype "passive"))
    )
    (net (code "65") (name "Net-(R1-2)") (class "Default")
      (node (ref "LEDB") (pin "C") (pinfunction "C_C") (pintype "passive"))
      (node (ref "R1") (pin "P$2") (pinfunction "2_P$2") (pintype "passive"))
    )
    (net (code "66") (name "Net-(R2-2)") (class "Default")
      (node (ref "LEDR") (pin "C") (pinfunction "C_C") (pintype "passive"))
      (node (ref "R2") (pin "P$2") (pinfunction "2_P$2") (pintype "passive"))
    )
    (net (code "67") (name "Net-(R3-2)") (class "Default")
      (node (ref "LEDG") (pin "C") (pinfunction "C_C") (pintype "passive"))
      (node (ref "R3") (pin "P$2") (pinfunction "2_P$2") (pintype "passive"))
    )
    (net (code "68") (name "Net-(R4-2)") (class "Default")
      (node (ref "LEDA") (pin "C") (pinfunction "C_C") (pintype "passive"))
      (node (ref "R4") (pin "P$2") (pinfunction "2_P$2") (pintype "passive"))
    )
    (net (code "69") (name "unconnected-(IC7-VREF-Pad5)") (class "Default")
      (node (ref "IC7") (pin "5") (pinfunction "VREF_5") (pintype "output"))
    )
    (net (code "70") (name "unconnected-(Q1-TRI-Pad1)") (class "Default")
      (node (ref "Q1") (pin "1") (pinfunction "TRI_1") (pintype "output"))
    )
  )
)
